# step-dir-opto.net
KiCad netlist of a schematic drawn in Altium Designer
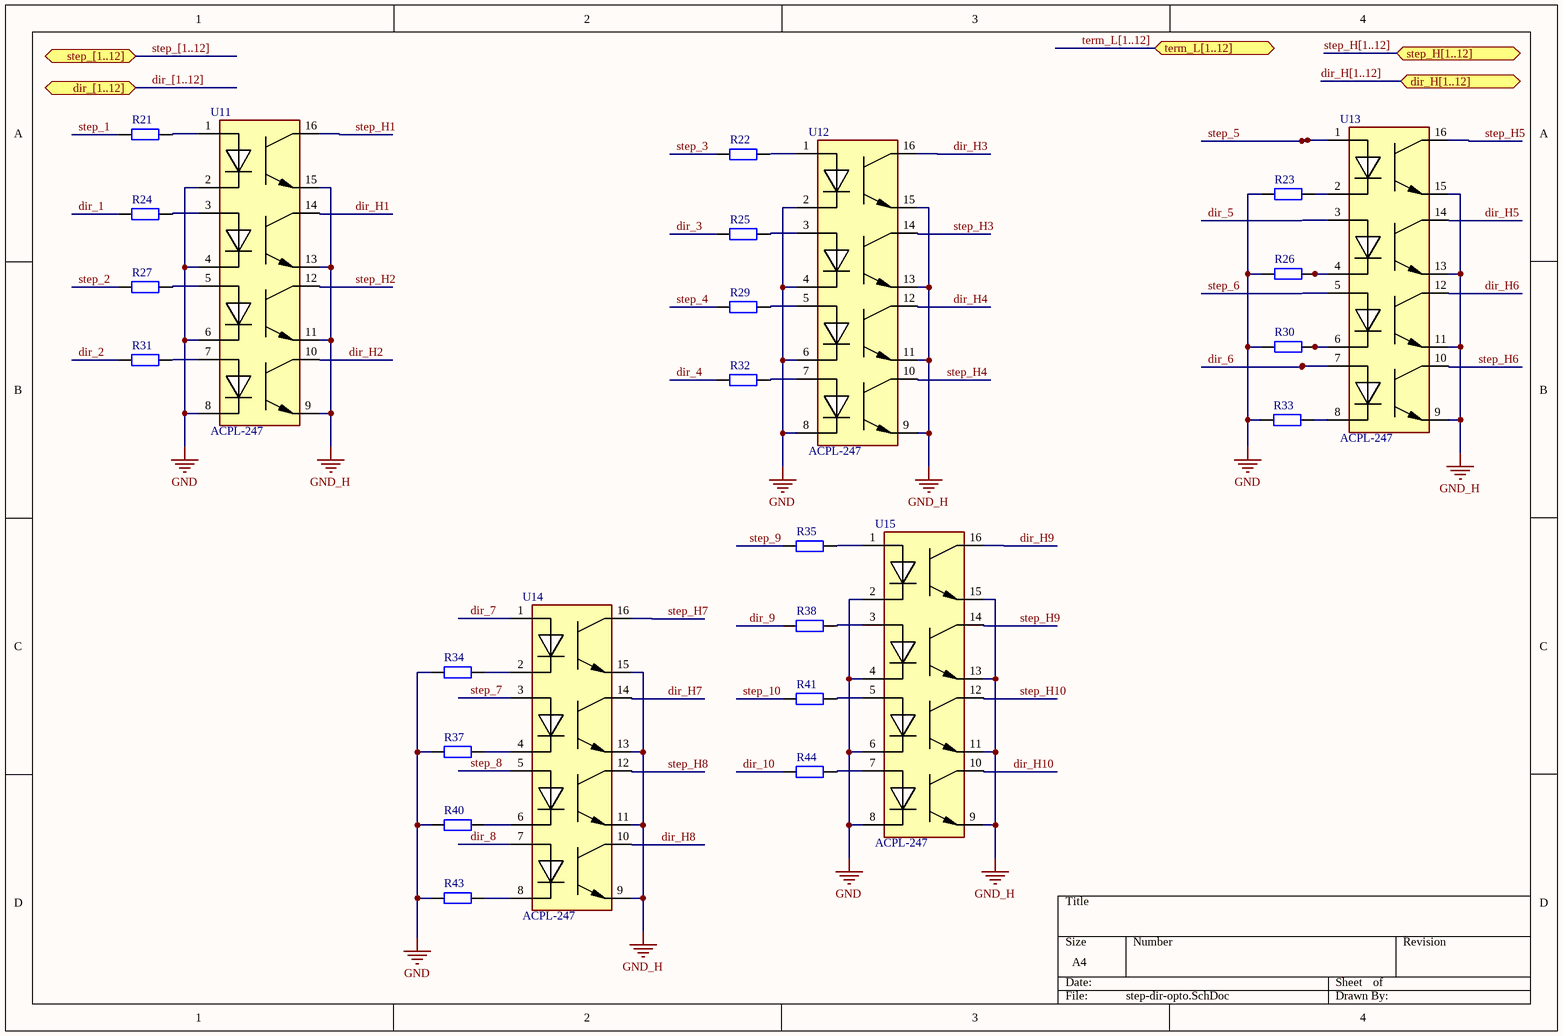
[diagram p0: step-dir-opto.SchDoc]

(export (version "E")
  (design (tool "Eeschema 10.0.6"))
  (components
    (comp (ref "R21")
      (value "Res2")
      (footprint "RESC2012M")
      (description "Resistor")
      (fields (field (name "PUBLISHER") "Altium Limited"))
      (libsource (lib "Miscellaneous Devices") (part "Res2"))
    )
    (comp (ref "R22")
      (value "Res2")
      (footprint "RESC2012M")
      (description "Resistor")
      (fields (field (name "PUBLISHER") "Altium Limited"))
      (libsource (lib "Miscellaneous Devices") (part "Res2"))
    )
    (comp (ref "R23")
      (value "Res2")
      (footprint "RESC2012M")
      (description "Resistor")
      (fields (field (name "PUBLISHER") "Altium Limited"))
      (libsource (lib "Miscellaneous Devices") (part "Res2"))
    )
    (comp (ref "R24")
      (value "Res2")
      (footprint "RESC2012M")
      (description "Resistor")
      (fields (field (name "PUBLISHER") "Altium Limited"))
      (libsource (lib "Miscellaneous Devices") (part "Res2"))
    )
    (comp (ref "R25")
      (value "Res2")
      (footprint "RESC2012M")
      (description "Resistor")
      (fields (field (name "PUBLISHER") "Altium Limited"))
      (libsource (lib "Miscellaneous Devices") (part "Res2"))
    )
    (comp (ref "R26")
      (value "Res2")
      (footprint "RESC2012M")
      (description "Resistor")
      (fields (field (name "PUBLISHER") "Altium Limited"))
      (libsource (lib "Miscellaneous Devices") (part "Res2"))
    )
    (comp (ref "R27")
      (value "Res2")
      (footprint "RESC2012M")
      (description "Resistor")
      (fields (field (name "PUBLISHER") "Altium Limited"))
      (libsource (lib "Miscellaneous Devices") (part "Res2"))
    )
    (comp (ref "R29")
      (value "Res2")
      (footprint "RESC2012M")
      (description "Resistor")
      (fields (field (name "PUBLISHER") "Altium Limited"))
      (libsource (lib "Miscellaneous Devices") (part "Res2"))
    )
    (comp (ref "R30")
      (value "Res2")
      (footprint "RESC2012M")
      (description "Resistor")
      (fields (field (name "PUBLISHER") "Altium Limited"))
      (libsource (lib "Miscellaneous Devices") (part "Res2"))
    )
    (comp (ref "R31")
      (value "Res2")
      (footprint "RESC2012M")
      (description "Resistor")
      (fields (field (name "PUBLISHER") "Altium Limited"))
      (libsource (lib "Miscellaneous Devices") (part "Res2"))
    )
    (comp (ref "R32")
      (value "Res2")
      (footprint "RESC2012M")
      (description "Resistor")
      (fields (field (name "PUBLISHER") "Altium Limited"))
      (libsource (lib "Miscellaneous Devices") (part "Res2"))
    )
    (comp (ref "R33")
      (value "Res2")
      (footprint "RESC2012M")
      (description "Resistor")
      (fields (field (name "PUBLISHER") "Altium Limited"))
      (libsource (lib "Miscellaneous Devices") (part "Res2"))
    )
    (comp (ref "R34")
      (value "Res2")
      (footprint "RESC2012M")
      (description "Resistor")
      (fields (field (name "PUBLISHER") "Altium Limited"))
      (libsource (lib "Miscellaneous Devices") (part "Res2"))
    )
    (comp (ref "R35")
      (value "Res2")
      (footprint "RESC2012M")
      (description "Resistor")
      (fields (field (name "PUBLISHER") "Altium Limited"))
      (libsource (lib "Miscellaneous Devices") (part "Res2"))
    )
    (comp (ref "R37")
      (value "Res2")
      (footprint "RESC2012M")
      (description "Resistor")
      (fields (field (name "PUBLISHER") "Altium Limited"))
      (libsource (lib "Miscellaneous Devices") (part "Res2"))
    )
    (comp (ref "R38")
      (value "Res2")
      (footprint "RESC2012M")
      (description "Resistor")
      (fields (field (name "PUBLISHER") "Altium Limited"))
      (libsource (lib "Miscellaneous Devices") (part "Res2"))
    )
    (comp (ref "R40")
      (value "Res2")
      (footprint "RESC2012M")
      (description "Resistor")
      (fields (field (name "PUBLISHER") "Altium Limited"))
      (libsource (lib "Miscellaneous Devices") (part "Res2"))
    )
    (comp (ref "R41")
      (value "Res2")
      (footprint "RESC2012M")
      (description "Resistor")
      (fields (field (name "PUBLISHER") "Altium Limited"))
      (libsource (lib "Miscellaneous Devices") (part "Res2"))
    )
    (comp (ref "R43")
      (value "Res2")
      (footprint "RESC2012M")
      (description "Resistor")
      (fields (field (name "PUBLISHER") "Altium Limited"))
      (libsource (lib "Miscellaneous Devices") (part "Res2"))
    )
    (comp (ref "R44")
      (value "Res2")
      (footprint "RESC2012M")
      (description "Resistor")
      (fields (field (name "PUBLISHER") "Altium Limited"))
      (libsource (lib "Miscellaneous Devices") (part "Res2"))
    )
    (comp (ref "U11")
      (value "ACPL-247")
      (footprint "SOIC127P600-16M")
      (description "DC Input Multi-Channel Half-Pitch  Phototransistor Optocoupler")
      (libsource (lib "Schlib1") (part "ACPL-247"))
    )
    (comp (ref "U12")
      (value "ACPL-247")
      (footprint "SOIC127P600-16M")
      (description "DC Input Multi-Channel Half-Pitch  Phototransistor Optocoupler")
      (libsource (lib "Schlib1") (part "ACPL-247"))
    )
    (comp (ref "U13")
      (value "ACPL-247")
      (footprint "SOIC127P600-16M")
      (description "DC Input Multi-Channel Half-Pitch  Phototransistor Optocoupler")
      (libsource (lib "Schlib1") (part "ACPL-247"))
    )
    (comp (ref "U14")
      (value "ACPL-247")
      (footprint "SOIC127P600-16M")
      (description "DC Input Multi-Channel Half-Pitch  Phototransistor Optocoupler")
      (libsource (lib "Schlib1") (part "ACPL-247"))
    )
    (comp (ref "U15")
      (value "ACPL-247")
      (footprint "SOIC127P600-16M")
      (description "DC Input Multi-Channel Half-Pitch  Phototransistor Optocoupler")
      (libsource (lib "Schlib1") (part "ACPL-247"))
    )
  )
  (nets
    (net (code "21") (name "/dir_1") (class "Default")
      (node (ref "R24") (pin "1") (pinfunction "1_1") (pintype "passive"))
    )
    (net (code "22") (name "/dir_2") (class "Default")
      (node (ref "R31") (pin "1") (pinfunction "1_1") (pintype "passive"))
    )
    (net (code "23") (name "/dir_3") (class "Default")
      (node (ref "R25") (pin "1") (pinfunction "1_1") (pintype "passive"))
    )
    (net (code "24") (name "/dir_4") (class "Default")
      (node (ref "R32") (pin "1") (pinfunction "1_1") (pintype "passive"))
    )
    (net (code "25") (name "/dir_5") (class "Default")
      (node (ref "U13") (pin "3") (pinfunction "3_3") (pintype "passive"))
    )
    (net (code "26") (name "/dir_6") (class "Default")
      (node (ref "U13") (pin "7") (pinfunction "7_7") (pintype "passive"))
    )
    (net (code "27") (name "/dir_7") (class "Default")
      (node (ref "U14") (pin "1") (pinfunction "1_1") (pintype "passive"))
    )
    (net (code "28") (name "/dir_8") (class "Default")
      (node (ref "U14") (pin "7") (pinfunction "7_7") (pintype "passive"))
    )
    (net (code "29") (name "/dir_9") (class "Default")
      (node (ref "R38") (pin "1") (pinfunction "1_1") (pintype "passive"))
    )
    (net (code "30") (name "/dir_10") (class "Default")
      (node (ref "R44") (pin "1") (pinfunction "1_1") (pintype "passive"))
    )
    (net (code "31") (name "/dir_H1") (class "Default")
      (node (ref "U11") (pin "14") (pinfunction "14_14") (pintype "passive"))
    )
    (net (code "32") (name "/dir_H2") (class "Default")
      (node (ref "U11") (pin "10") (pinfunction "10_10") (pintype "passive"))
    )
    (net (code "33") (name "/dir_H3") (class "Default")
      (node (ref "U12") (pin "16") (pinfunction "16_16") (pintype "passive"))
    )
    (net (code "34") (name "/dir_H4") (class "Default")
      (node (ref "U12") (pin "12") (pinfunction "12_12") (pintype "passive"))
    )
    (net (code "35") (name "/dir_H5") (class "Default")
      (node (ref "U13") (pin "14") (pinfunction "14_14") (pintype "passive"))
    )
    (net (code "36") (name "/dir_H6") (class "Default")
      (node (ref "U13") (pin "12") (pinfunction "12_12") (pintype "passive"))
    )
    (net (code "37") (name "/dir_H7") (class "Default")
      (node (ref "U14") (pin "14") (pinfunction "14_14") (pintype "passive"))
    )
    (net (code "38") (name "/dir_H8") (class "Default")
      (node (ref "U14") (pin "10") (pinfunction "10_10") (pintype "passive"))
    )
    (net (code "39") (name "/dir_H9") (class "Default")
      (node (ref "U15") (pin "16") (pinfunction "16_16") (pintype "passive"))
    )
    (net (code "40") (name "/dir_H10") (class "Default")
      (node (ref "U15") (pin "10") (pinfunction "10_10") (pintype "passive"))
    )
    (net (code "43") (name "/step_1") (class "Default")
      (node (ref "R21") (pin "1") (pinfunction "1_1") (pintype "passive"))
    )
    (net (code "44") (name "/step_2") (class "Default")
      (node (ref "R27") (pin "1") (pinfunction "1_1") (pintype "passive"))
    )
    (net (code "45") (name "/step_3") (class "Default")
      (node (ref "R22") (pin "1") (pinfunction "1_1") (pintype "passive"))
    )
    (net (code "46") (name "/step_4") (class "Default")
      (node (ref "R29") (pin "1") (pinfunction "1_1") (pintype "passive"))
    )
    (net (code "47") (name "/step_5") (class "Default")
      (node (ref "U13") (pin "1") (pinfunction "1_1") (pintype "passive"))
    )
    (net (code "48") (name "/step_6") (class "Default")
      (node (ref "U13") (pin "5") (pinfunction "5_5") (pintype "passive"))
    )
    (net (code "49") (name "/step_7") (class "Default")
      (node (ref "U14") (pin "3") (pinfunction "3_3") (pintype "passive"))
    )
    (net (code "50") (name "/step_8") (class "Default")
      (node (ref "U14") (pin "5") (pinfunction "5_5") (pintype "passive"))
    )
    (net (code "51") (name "/step_9") (class "Default")
      (node (ref "R35") (pin "1") (pinfunction "1_1") (pintype "passive"))
    )
    (net (code "52") (name "/step_10") (class "Default")
      (node (ref "R41") (pin "1") (pinfunction "1_1") (pintype "passive"))
    )
    (net (code "53") (name "/step_H1") (class "Default")
      (node (ref "U11") (pin "16") (pinfunction "16_16") (pintype "passive"))
    )
    (net (code "54") (name "/step_H2") (class "Default")
      (node (ref "U11") (pin "12") (pinfunction "12_12") (pintype "passive"))
    )
    (net (code "55") (name "/step_H3") (class "Default")
      (node (ref "U12") (pin "14") (pinfunction "14_14") (pintype "passive"))
    )
    (net (code "56") (name "/step_H4") (class "Default")
      (node (ref "U12") (pin "10") (pinfunction "10_10") (pintype "passive"))
    )
    (net (code "57") (name "/step_H5") (class "Default")
      (node (ref "U13") (pin "16") (pinfunction "16_16") (pintype "passive"))
    )
    (net (code "58") (name "/step_H6") (class "Default")
      (node (ref "U13") (pin "10") (pinfunction "10_10") (pintype "passive"))
    )
    (net (code "59") (name "/step_H7") (class "Default")
      (node (ref "U14") (pin "16") (pinfunction "16_16") (pintype "passive"))
    )
    (net (code "60") (name "/step_H8") (class "Default")
      (node (ref "U14") (pin "12") (pinfunction "12_12") (pintype "passive"))
    )
    (net (code "61") (name "/step_H9") (class "Default")
      (node (ref "U15") (pin "14") (pinfunction "14_14") (pintype "passive"))
    )
    (net (code "62") (name "/step_H10") (class "Default")
      (node (ref "U15") (pin "12") (pinfunction "12_12") (pintype "passive"))
    )
    (net (code "66") (name "GND") (class "Default")
      (node (ref "R23") (pin "1") (pinfunction "1_1") (pintype "passive"))
      (node (ref "R26") (pin "1") (pinfunction "1_1") (pintype "passive"))
      (node (ref "R30") (pin "1") (pinfunction "1_1") (pintype "passive"))
      (node (ref "R33") (pin "1") (pinfunction "1_1") (pintype "passive"))
      (node (ref "R34") (pin "1") (pinfunction "1_1") (pintype "passive"))
      (node (ref "R37") (pin "1") (pinfunction "1_1") (pintype "passive"))
      (node (ref "R40") (pin "1") (pinfunction "1_1") (pintype "passive"))
      (node (ref "R43") (pin "1") (pinfunction "1_1") (pintype "passive"))
      (node (ref "U11") (pin "2") (pinfunction "2_2") (pintype "passive"))
      (node (ref "U11") (pin "4") (pinfunction "4_4") (pintype "passive"))
      (node (ref "U11") (pin "6") (pinfunction "6_6") (pintype "passive"))
      (node (ref "U11") (pin "8") (pinfunction "8_8") (pintype "passive"))
      (node (ref "U12") (pin "2") (pinfunction "2_2") (pintype "passive"))
      (node (ref "U12") (pin "4") (pinfunction "4_4") (pintype "passive"))
      (node (ref "U12") (pin "6") (pinfunction "6_6") (pintype "passive"))
      (node (ref "U12") (pin "8") (pinfunction "8_8") (pintype "passive"))
      (node (ref "U15") (pin "2") (pinfunction "2_2") (pintype "passive"))
      (node (ref "U15") (pin "4") (pinfunction "4_4") (pintype "passive"))
      (node (ref "U15") (pin "6") (pinfunction "6_6") (pintype "passive"))
      (node (ref "U15") (pin "8") (pinfunction "8_8") (pintype "passive"))
    )
    (net (code "67") (name "GND_H") (class "Default")
      (node (ref "U11") (pin "11") (pinfunction "11_11") (pintype "passive"))
      (node (ref "U11") (pin "13") (pinfunction "13_13") (pintype "passive"))
      (node (ref "U11") (pin "15") (pinfunction "15_15") (pintype "passive"))
      (node (ref "U11") (pin "9") (pinfunction "9_9") (pintype "passive"))
      (node (ref "U12") (pin "11") (pinfunction "11_11") (pintype "passive"))
      (node (ref "U12") (pin "13") (pinfunction "13_13") (pintype "passive"))
      (node (ref "U12") (pin "15") (pinfunction "15_15") (pintype "passive"))
      (node (ref "U12") (pin "9") (pinfunction "9_9") (pintype "passive"))
      (node (ref "U13") (pin "11") (pinfunction "11_11") (pintype "passive"))
      (node (ref "U13") (pin "13") (pinfunction "13_13") (pintype "passive"))
      (node (ref "U13") (pin "15") (pinfunction "15_15") (pintype "passive"))
      (node (ref "U13") (pin "9") (pinfunction "9_9") (pintype "passive"))
      (node (ref "U14") (pin "11") (pinfunction "11_11") (pintype "passive"))
      (node (ref "U14") (pin "13") (pinfunction "13_13") (pintype "passive"))
      (node (ref "U14") (pin "15") (pinfunction "15_15") (pintype "passive"))
      (node (ref "U14") (pin "9") (pinfunction "9_9") (pintype "passive"))
      (node (ref "U15") (pin "11") (pinfunction "11_11") (pintype "passive"))
      (node (ref "U15") (pin "13") (pinfunction "13_13") (pintype "passive"))
      (node (ref "U15") (pin "15") (pinfunction "15_15") (pintype "passive"))
      (node (ref "U15") (pin "9") (pinfunction "9_9") (pintype "passive"))
    )
    (net (code "68") (name "Net-(R21-Pad2)") (class "Default")
      (node (ref "R21") (pin "2") (pinfunction "2_2") (pintype "passive"))
      (node (ref "U11") (pin "1") (pinfunction "1_1") (pintype "passive"))
    )
    (net (code "69") (name "Net-(R22-Pad2)") (class "Default")
      (node (ref "R22") (pin "2") (pinfunction "2_2") (pintype "passive"))
      (node (ref "U12") (pin "1") (pinfunction "1_1") (pintype "passive"))
    )
    (net (code "70") (name "Net-(R23-Pad2)") (class "Default")
      (node (ref "R23") (pin "2") (pinfunction "2_2") (pintype "passive"))
      (node (ref "U13") (pin "2") (pinfunction "2_2") (pintype "passive"))
    )
    (net (code "71") (name "Net-(R24-Pad2)") (class "Default")
      (node (ref "R24") (pin "2") (pinfunction "2_2") (pintype "passive"))
      (node (ref "U11") (pin "3") (pinfunction "3_3") (pintype "passive"))
    )
    (net (code "72") (name "Net-(R25-Pad2)") (class "Default")
      (node (ref "R25") (pin "2") (pinfunction "2_2") (pintype "passive"))
      (node (ref "U12") (pin "3") (pinfunction "3_3") (pintype "passive"))
    )
    (net (code "73") (name "Net-(R26-Pad2)") (class "Default")
      (node (ref "R26") (pin "2") (pinfunction "2_2") (pintype "passive"))
      (node (ref "U13") (pin "4") (pinfunction "4_4") (pintype "passive"))
    )
    (net (code "74") (name "Net-(R27-Pad2)") (class "Default")
      (node (ref "R27") (pin "2") (pinfunction "2_2") (pintype "passive"))
      (node (ref "U11") (pin "5") (pinfunction "5_5") (pintype "passive"))
    )
    (net (code "75") (name "Net-(R29-Pad2)") (class "Default")
      (node (ref "R29") (pin "2") (pinfunction "2_2") (pintype "passive"))
      (node (ref "U12") (pin "5") (pinfunction "5_5") (pintype "passive"))
    )
    (net (code "76") (name "Net-(R30-Pad2)") (class "Default")
      (node (ref "R30") (pin "2") (pinfunction "2_2") (pintype "passive"))
      (node (ref "U13") (pin "6") (pinfunction "6_6") (pintype "passive"))
    )
    (net (code "77") (name "Net-(R31-Pad2)") (class "Default")
      (node (ref "R31") (pin "2") (pinfunction "2_2") (pintype "passive"))
      (node (ref "U11") (pin "7") (pinfunction "7_7") (pintype "passive"))
    )
    (net (code "78") (name "Net-(R32-Pad2)") (class "Default")
      (node (ref "R32") (pin "2") (pinfunction "2_2") (pintype "passive"))
      (node (ref "U12") (pin "7") (pinfunction "7_7") (pintype "passive"))
    )
    (net (code "79") (name "Net-(R33-Pad2)") (class "Default")
      (node (ref "R33") (pin "2") (pinfunction "2_2") (pintype "passive"))
      (node (ref "U13") (pin "8") (pinfunction "8_8") (pintype "passive"))
    )
    (net (code "80") (name "Net-(R34-Pad2)") (class "Default")
      (node (ref "R34") (pin "2") (pinfunction "2_2") (pintype "passive"))
      (node (ref "U14") (pin "2") (pinfunction "2_2") (pintype "passive"))
    )
    (net (code "81") (name "Net-(R35-Pad2)") (class "Default")
      (node (ref "R35") (pin "2") (pinfunction "2_2") (pintype "passive"))
      (node (ref "U15") (pin "1") (pinfunction "1_1") (pintype "passive"))
    )
    (net (code "82") (name "Net-(R37-Pad2)") (class "Default")
      (node (ref "R37") (pin "2") (pinfunction "2_2") (pintype "passive"))
      (node (ref "U14") (pin "4") (pinfunction "4_4") (pintype "passive"))
    )
    (net (code "83") (name "Net-(R38-Pad2)") (class "Default")
      (node (ref "R38") (pin "2") (pinfunction "2_2") (pintype "passive"))
      (node (ref "U15") (pin "3") (pinfunction "3_3") (pintype "passive"))
    )
    (net (code "84") (name "Net-(R40-Pad2)") (class "Default")
      (node (ref "R40") (pin "2") (pinfunction "2_2") (pintype "passive"))
      (node (ref "U14") (pin "6") (pinfunction "6_6") (pintype "passive"))
    )
    (net (code "85") (name "Net-(R41-Pad2)") (class "Default")
      (node (ref "R41") (pin "2") (pinfunction "2_2") (pintype "passive"))
      (node (ref "U15") (pin "5") (pinfunction "5_5") (pintype "passive"))
    )
    (net (code "86") (name "Net-(R43-Pad2)") (class "Default")
      (node (ref "R43") (pin "2") (pinfunction "2_2") (pintype "passive"))
      (node (ref "U14") (pin "8") (pinfunction "8_8") (pintype "passive"))
    )
    (net (code "87") (name "Net-(R44-Pad2)") (class "Default")
      (node (ref "R44") (pin "2") (pinfunction "2_2") (pintype "passive"))
      (node (ref "U15") (pin "7") (pinfunction "7_7") (pintype "passive"))
    )
  )
)
